# INA226-Current-Sensors.net
KiCad netlist of a schematic drawn in Altium Designer
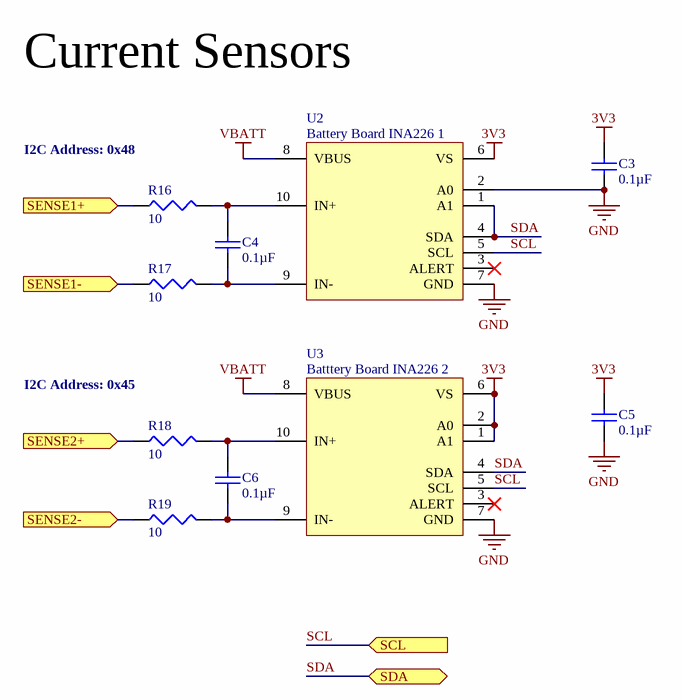
[diagram p0: INA226-Current-Sensors.SchDoc]

(export (version "E")
  (design (tool "Eeschema 10.0.6"))
  (components
    (comp (ref "C3")
      (value "0.1µF")
      (footprint "TDK-CGA2B")
      (description "CAP CER 0.1UF 50V X7R 0402")
      (fields
        (field (name "PART NUMBER") "PC-TDK-02262")
        (field (name "MANUFACTURER PART NUMBER") "CGA2B3X7R1H104M050BB")
        (field (name "PUBLISHER") "AlbertaSat")
      )
      (libsource (lib "Database") (part "Cap"))
    )
    (comp (ref "C4")
      (value "0.1µF")
      (footprint "TDK-CGA5L")
      (description "CAP CER 0.1UF 50V NP0 1206")
      (fields
        (field (name "PART NUMBER") "PC-TDK-02295")
        (field (name "MANUFACTURER PART NUMBER") "CGA5L2NP01H104J160AA")
        (field (name "PUBLISHER") "AlbertaSat")
      )
      (libsource (lib "Database") (part "Cap"))
    )
    (comp (ref "C5")
      (value "0.1µF")
      (footprint "TDK-CGA2B")
      (description "CAP CER 0.1UF 50V X7R 0402")
      (fields
        (field (name "PART NUMBER") "PC-TDK-02262")
        (field (name "MANUFACTURER PART NUMBER") "CGA2B3X7R1H104M050BB")
        (field (name "PUBLISHER") "AlbertaSat")
      )
      (libsource (lib "Database") (part "Cap"))
    )
    (comp (ref "C6")
      (value "0.1µF")
      (footprint "TDK-CGA5L")
      (description "CAP CER 0.1UF 50V NP0 1206")
      (fields
        (field (name "PART NUMBER") "PC-TDK-02295")
        (field (name "MANUFACTURER PART NUMBER") "CGA5L2NP01H104J160AA")
        (field (name "PUBLISHER") "AlbertaSat")
      )
      (libsource (lib "Database") (part "Cap"))
    )
    (comp (ref "R16")
      (value "10")
      (footprint "PANA-ERA2A")
      (description "RES SMD 10 OHM 0.5% 1/16W 0402")
      (fields
        (field (name "PART NUMBER") "13235")
        (field (name "MANUFACTURER PART NUMBER") "ERA-2AKD100X")
        (field (name "PUBLISHER") "Altium Limited")
      )
      (libsource (lib "Database") (part "Res3"))
    )
    (comp (ref "R17")
      (value "10")
      (footprint "PANA-ERA2A")
      (description "RES SMD 10 OHM 0.5% 1/16W 0402")
      (fields
        (field (name "PART NUMBER") "13235")
        (field (name "MANUFACTURER PART NUMBER") "ERA-2AKD100X")
        (field (name "PUBLISHER") "Altium Limited")
      )
      (libsource (lib "Database") (part "Res3"))
    )
    (comp (ref "R18")
      (value "10")
      (footprint "PANA-ERA2A")
      (description "RES SMD 10 OHM 0.5% 1/16W 0402")
      (fields
        (field (name "PART NUMBER") "13235")
        (field (name "MANUFACTURER PART NUMBER") "ERA-2AKD100X")
        (field (name "PUBLISHER") "Altium Limited")
      )
      (libsource (lib "Database") (part "Res3"))
    )
    (comp (ref "R19")
      (value "10")
      (footprint "PANA-ERA2A")
      (description "RES SMD 10 OHM 0.5% 1/16W 0402")
      (fields
        (field (name "PART NUMBER") "13235")
        (field (name "MANUFACTURER PART NUMBER") "ERA-2AKD100X")
        (field (name "PUBLISHER") "Altium Limited")
      )
      (libsource (lib "Database") (part "Res3"))
    )
    (comp (ref "U2")
      (value "Battery Board INA226 1")
      (footprint "TI-DGS")
      (description "IC MONITOR PWR/CURR BIDIR 10MSOP")
      (fields (field (name "PART NUMBER") "19") (field (name "MANUFACTURER PART NUMBER") "INA226AQDGSRQ1"))
      (libsource (lib "Database") (part "INA226AQ"))
    )
    (comp (ref "U3")
      (value "Batttery Board INA226 2")
      (footprint "TI-DGS")
      (description "IC MONITOR PWR/CURR BIDIR 10MSOP")
      (fields (field (name "PART NUMBER") "19") (field (name "MANUFACTURER PART NUMBER") "INA226AQDGSRQ1"))
      (libsource (lib "Database") (part "INA226AQ"))
    )
  )
  (nets
    (net (code "2") (name "/SCL") (class "Default")
      (node (ref "U2") (pin "5") (pinfunction "SCL_5") (pintype "passive"))
      (node (ref "U3") (pin "5") (pinfunction "SCL_5") (pintype "passive"))
    )
    (net (code "3") (name "/SDA") (class "Default")
      (node (ref "U2") (pin "1") (pinfunction "A1_1") (pintype "passive"))
      (node (ref "U2") (pin "4") (pinfunction "SDA_4") (pintype "passive"))
      (node (ref "U3") (pin "4") (pinfunction "SDA_4") (pintype "passive"))
    )
    (net (code "4") (name "/SENSE1+") (class "Default")
      (node (ref "R16") (pin "1") (pinfunction "1_1") (pintype "passive"))
    )
    (net (code "5") (name "/SENSE1-") (class "Default")
      (node (ref "R17") (pin "1") (pinfunction "1_1") (pintype "passive"))
    )
    (net (code "6") (name "/SENSE2+") (class "Default")
      (node (ref "R18") (pin "1") (pinfunction "1_1") (pintype "passive"))
    )
    (net (code "7") (name "/SENSE2-") (class "Default")
      (node (ref "R19") (pin "1") (pinfunction "1_1") (pintype "passive"))
    )
    (net (code "8") (name "3V3") (class "Default")
      (node (ref "C3") (pin "2") (pinfunction "2_2") (pintype "passive"))
      (node (ref "C5") (pin "2") (pinfunction "2_2") (pintype "passive"))
      (node (ref "U2") (pin "6") (pinfunction "VS_6") (pintype "passive"))
      (node (ref "U3") (pin "1") (pinfunction "A1_1") (pintype "passive"))
      (node (ref "U3") (pin "2") (pinfunction "A0_2") (pintype "passive"))
      (node (ref "U3") (pin "6") (pinfunction "VS_6") (pintype "passive"))
    )
    (net (code "9") (name "GND") (class "Default")
      (node (ref "C3") (pin "1") (pinfunction "1_1") (pintype "passive"))
      (node (ref "C5") (pin "1") (pinfunction "1_1") (pintype "passive"))
      (node (ref "U2") (pin "2") (pinfunction "A0_2") (pintype "passive"))
      (node (ref "U2") (pin "7") (pinfunction "GND_7") (pintype "passive"))
      (node (ref "U3") (pin "7") (pinfunction "GND_7") (pintype "passive"))
    )
    (net (code "10") (name "Net-(U2-IN+)") (class "Default")
      (node (ref "C4") (pin "2") (pinfunction "2_2") (pintype "passive"))
      (node (ref "R16") (pin "2") (pinfunction "2_2") (pintype "passive"))
      (node (ref "U2") (pin "10") (pinfunction "IN+_10") (pintype "passive"))
    )
    (net (code "11") (name "Net-(U2-IN-)") (class "Default")
      (node (ref "C4") (pin "1") (pinfunction "1_1") (pintype "passive"))
      (node (ref "R17") (pin "2") (pinfunction "2_2") (pintype "passive"))
      (node (ref "U2") (pin "9") (pinfunction "IN-_9") (pintype "passive"))
    )
    (net (code "12") (name "Net-(U3-IN+)") (class "Default")
      (node (ref "C6") (pin "2") (pinfunction "2_2") (pintype "passive"))
      (node (ref "R18") (pin "2") (pinfunction "2_2") (pintype "passive"))
      (node (ref "U3") (pin "10") (pinfunction "IN+_10") (pintype "passive"))
    )
    (net (code "13") (name "Net-(U3-IN-)") (class "Default")
      (node (ref "C6") (pin "1") (pinfunction "1_1") (pintype "passive"))
      (node (ref "R19") (pin "2") (pinfunction "2_2") (pintype "passive"))
      (node (ref "U3") (pin "9") (pinfunction "IN-_9") (pintype "passive"))
    )
    (net (code "14") (name "VBATT") (class "Default")
      (node (ref "U2") (pin "8") (pinfunction "VBUS_8") (pintype "passive"))
      (node (ref "U3") (pin "8") (pinfunction "VBUS_8") (pintype "passive"))
    )
    (net (code "15") (name "unconnected-(U2-ALERT-Pad3)") (class "Default")
      (node (ref "U2") (pin "3") (pinfunction "ALERT_3") (pintype "passive+no_connect"))
    )
    (net (code "16") (name "unconnected-(U3-ALERT-Pad3)") (class "Default")
      (node (ref "U3") (pin "3") (pinfunction "ALERT_3") (pintype "passive+no_connect"))
    )
  )
)
